# LCDCircuit.net
KiCad netlist of a schematic drawn in Altium Designer
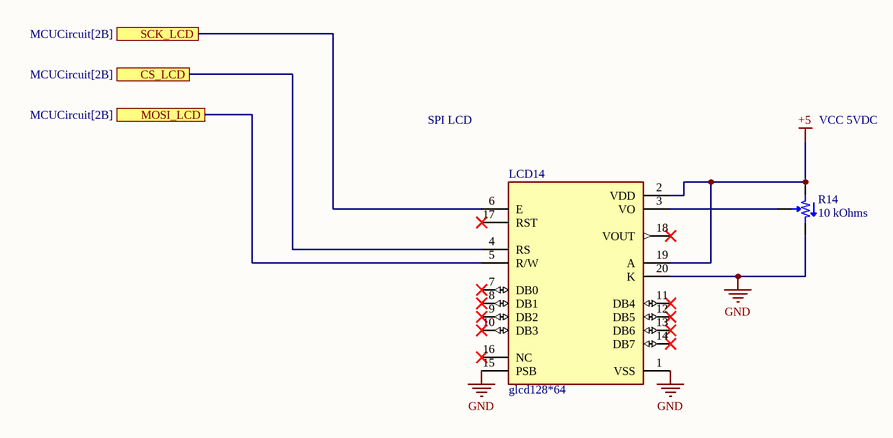
[diagram p0: LCDCircuit.SchDoc]

(export (version "E")
  (design (tool "Eeschema 10.0.6"))
  (components
    (comp (ref "LCD14")
      (value "glcd128*64")
      (footprint "GLCD128*64")
      (libsource (lib "GLCD12864") (part "glcd128*64"))
    )
    (comp (ref "R14")
      (value "10 kOhms")
      (footprint "BOURNS TRIMPOT 3386P-1")
      (description "TRIMMER 10K OHM 0.5W PC PIN TOP")
      (fields (field (name "PART NUMBER") "3386P-1-103LF") (field (name "MANUFACTURER") "Bourns Inc."))
      (libsource (lib "Celestial Altium Library - altium_library") (part "Potentiometer"))
    )
  )
  (nets
    (net (code "1") (name "+5") (class "Default")
      (node (ref "LCD14") (pin "19") (pinfunction "A_19") (pintype "passive"))
      (node (ref "LCD14") (pin "2") (pinfunction "VDD_2") (pintype "power_in"))
      (node (ref "R14") (pin "1") (pinfunction "1_1") (pintype "passive"))
    )
    (net (code "2") (name "/CS_LCD") (class "Default")
      (node (ref "LCD14") (pin "4") (pinfunction "RS_4") (pintype "passive"))
    )
    (net (code "3") (name "/MOSI_LCD") (class "Default")
      (node (ref "LCD14") (pin "5") (pinfunction "R/W_5") (pintype "passive"))
    )
    (net (code "4") (name "/SCK_LCD") (class "Default")
      (node (ref "LCD14") (pin "6") (pinfunction "E_6") (pintype "passive"))
    )
    (net (code "5") (name "GND") (class "Default")
      (node (ref "LCD14") (pin "1") (pinfunction "VSS_1") (pintype "power_in"))
      (node (ref "LCD14") (pin "15") (pinfunction "PSB_15") (pintype "passive"))
      (node (ref "LCD14") (pin "20") (pinfunction "K_20") (pintype "passive"))
      (node (ref "R14") (pin "3") (pinfunction "3_3") (pintype "passive"))
    )
    (net (code "6") (name "Net-(LCD14-VO)") (class "Default")
      (node (ref "LCD14") (pin "3") (pinfunction "VO_3") (pintype "power_in"))
      (node (ref "R14") (pin "2") (pinfunction "2_2") (pintype "passive"))
    )
    (net (code "7") (name "unconnected-(LCD14-DB0-Pad7)") (class "Default")
      (node (ref "LCD14") (pin "7") (pinfunction "DB0_7") (pintype "bidirectional+no_connect"))
    )
    (net (code "8") (name "unconnected-(LCD14-DB1-Pad8)") (class "Default")
      (node (ref "LCD14") (pin "8") (pinfunction "DB1_8") (pintype "bidirectional+no_connect"))
    )
    (net (code "9") (name "unconnected-(LCD14-DB2-Pad9)") (class "Default")
      (node (ref "LCD14") (pin "9") (pinfunction "DB2_9") (pintype "bidirectional+no_connect"))
    )
    (net (code "10") (name "unconnected-(LCD14-DB3-Pad10)") (class "Default")
      (node (ref "LCD14") (pin "10") (pinfunction "DB3_10") (pintype "bidirectional+no_connect"))
    )
    (net (code "11") (name "unconnected-(LCD14-DB4-Pad11)") (class "Default")
      (node (ref "LCD14") (pin "11") (pinfunction "DB4_11") (pintype "bidirectional+no_connect"))
    )
    (net (code "12") (name "unconnected-(LCD14-DB5-Pad12)") (class "Default")
      (node (ref "LCD14") (pin "12") (pinfunction "DB5_12") (pintype "bidirectional+no_connect"))
    )
    (net (code "13") (name "unconnected-(LCD14-DB6-Pad13)") (class "Default")
      (node (ref "LCD14") (pin "13") (pinfunction "DB6_13") (pintype "bidirectional+no_connect"))
    )
    (net (code "14") (name "unconnected-(LCD14-DB7-Pad14)") (class "Default")
      (node (ref "LCD14") (pin "14") (pinfunction "DB7_14") (pintype "bidirectional+no_connect"))
    )
    (net (code "15") (name "unconnected-(LCD14-NC-Pad16)") (class "Default")
      (node (ref "LCD14") (pin "16") (pinfunction "NC_16") (pintype "passive+no_connect"))
    )
    (net (code "16") (name "unconnected-(LCD14-RST-Pad17)") (class "Default")
      (node (ref "LCD14") (pin "17") (pinfunction "RST_17") (pintype "passive+no_connect"))
    )
    (net (code "17") (name "unconnected-(LCD14-VOUT-Pad18)") (class "Default")
      (node (ref "LCD14") (pin "18") (pinfunction "VOUT_18") (pintype "output+no_connect"))
    )
  )
)
